# Power_supply.net
KiCad netlist of a schematic drawn in Altium Designer
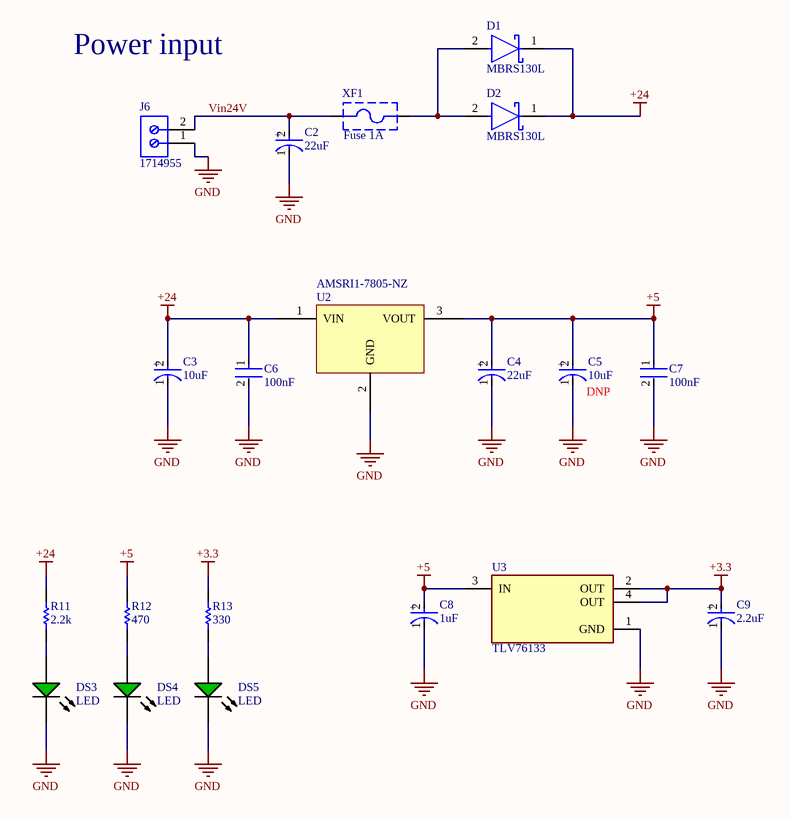
[diagram p0: Power_supply.SchDoc]

(export (version "E")
  (design (tool "Eeschema 10.0.6"))
  (components
    (comp (ref "C2")
      (value "22uF")
      (footprint "FP-FCE-MFG")
      (description "CAP ALUM 22UF 20% 50V SMD")
      (fields (field (name "VOLTAGE") "50V") (field (name "TOLERANCE") "20%"))
      (libsource (lib "Altium Content Vault") (part "a00bbbee19879c290e62620ae7e47b1"))
    )
    (comp (ref "C3")
      (value "10uF")
      (footprint "FP-FKD-MFG")
      (description "CAP ALUM 10UF 20% 50V SMD")
      (fields (field (name "VOLTAGE") "50V") (field (name "TOLERANCE") "20%"))
      (libsource (lib "Altium Content Vault") (part "203bc49f2ac43e59fd269a8c329ed05"))
    )
    (comp (ref "C4")
      (value "22uF")
      (footprint "FP-FCE-MFG")
      (description "CAP ALUM 22UF 20% 50V SMD")
      (fields (field (name "VOLTAGE") "50V") (field (name "TOLERANCE") "20%"))
      (libsource (lib "Altium Content Vault") (part "a00bbbee19879c290e62620ae7e47b1"))
    )
    (comp (ref "C5")
      (value "10uF")
      (footprint "FP-FKD-MFG")
      (description "CAP ALUM 10UF 20% 50V SMD")
      (fields (field (name "VOLTAGE") "50V") (field (name "TOLERANCE") "20%"))
      (libsource (lib "Altium Content Vault") (part "203bc49f2ac43e59fd269a8c329ed05"))
    )
    (comp (ref "C6")
      (value "100nF")
      (footprint "FP-0805-L_2_01_0_2-W_1_25-IPC_B")
      (description "General Purpose Ceramic Capacitor, 0805, 10nF, 10%, X7R, 15%, 100V")
      (fields (field (name "VOLTAGE") "100V") (field (name "TOLERANCE") "10%"))
      (libsource (lib "Altium Content Vault") (part "b4654b650e69147ec39a6b967a45e02"))
    )
    (comp (ref "C7")
      (value "100nF")
      (footprint "FP-0805-L_2_01_0_2-W_1_25-IPC_B")
      (description "General Purpose Ceramic Capacitor, 0805, 10nF, 10%, X7R, 15%, 100V")
      (fields (field (name "VOLTAGE") "100V") (field (name "TOLERANCE") "10%"))
      (libsource (lib "Altium Content Vault") (part "b4654b650e69147ec39a6b967a45e02"))
    )
    (comp (ref "C8")
      (value "1uF")
      (footprint "FP-FKD-MFG")
      (description "CAP ALUM 10UF 20% 50V SMD")
      (fields (field (name "VOLTAGE") "50V") (field (name "TOLERANCE") "20%"))
      (libsource (lib "Altium Content Vault") (part "203bc49f2ac43e59fd269a8c329ed05"))
    )
    (comp (ref "C9")
      (value "2.2uF")
      (footprint "FP-FKD-MFG")
      (description "CAP ALUM 10UF 20% 50V SMD")
      (fields (field (name "VOLTAGE") "50V") (field (name "TOLERANCE") "20%"))
      (libsource (lib "Altium Content Vault") (part "203bc49f2ac43e59fd269a8c329ed05"))
    )
    (comp (ref "D1")
      (value "MBRS130L")
      (footprint "FP-403AF-MFG")
      (description "MBRS130L Rectifier Diode, Schottky, 1 Phase, 1 Element, 2A, 30V V(RRM), Silicon, DO-214AA")
      (libsource (lib "Altium Content Vault") (part "1d6ec82d83fb6aee721767c19dac4b9"))
    )
    (comp (ref "D2")
      (value "MBRS130L")
      (footprint "FP-403AF-MFG")
      (description "MBRS130L Rectifier Diode, Schottky, 1 Phase, 1 Element, 2A, 30V V(RRM), Silicon, DO-214AA")
      (libsource (lib "Altium Content Vault") (part "1d6ec82d83fb6aee721767c19dac4b9"))
    )
    (comp (ref "DS3")
      (value "LED")
      (footprint "AVAG-HSMX-C170_V")
      (description "Chip LED, Green, 2.2 V, -40 to 85 degC, 2-Pin SMD, Pb-Free, Tape and Reel")
      (fields (field (name "MANUFACTURER") "Avago"))
      (libsource (lib "Altium Content Vault") (part "LED_GREEN_A1K2-2"))
    )
    (comp (ref "DS4")
      (value "LED")
      (footprint "AVAG-HSMX-C170_V")
      (description "Chip LED, Green, 2.2 V, -40 to 85 degC, 2-Pin SMD, Pb-Free, Tape and Reel")
      (fields (field (name "MANUFACTURER") "Avago"))
      (libsource (lib "Altium Content Vault") (part "LED_GREEN_A1K2-2"))
    )
    (comp (ref "DS5")
      (value "LED")
      (footprint "AVAG-HSMX-C170_V")
      (description "Chip LED, Green, 2.2 V, -40 to 85 degC, 2-Pin SMD, Pb-Free, Tape and Reel")
      (fields (field (name "MANUFACTURER") "Avago"))
      (libsource (lib "Altium Content Vault") (part "LED_GREEN_A1K2-2"))
    )
    (comp (ref "J6")
      (value "1714955")
      (footprint "PHOE-1714955_V")
      (description "PC Terminal Block, Pitch 6.35 mm, 1 x 2 Position, Height 21.5 mm, Tail Lenght 5.1 mm, RoHS, Bulk")
      (fields (field (name "MANUFACTURER") "Phoenix Contact"))
      (libsource (lib "Altium Content Vault") (part "CN-1P-F-TB2"))
    )
    (comp (ref "R11")
      (value "2.2k")
      (footprint "RESC2013X50X30LL20T20")
      (fields (field (name "MANUFACTURER") "Vishay Dale") (field (name "PART NUMBER") "CRCW08050000Z0EA"))
      (libsource (lib "Altium Content Vault") (part "RES"))
    )
    (comp (ref "R12")
      (value "470")
      (footprint "RESC2013X50X30LL20T20")
      (fields (field (name "MANUFACTURER") "Vishay Dale") (field (name "PART NUMBER") "CRCW08050000Z0EA"))
      (libsource (lib "Altium Content Vault") (part "RES"))
    )
    (comp (ref "R13")
      (value "330")
      (footprint "RESC2013X50X30LL20T20")
      (fields (field (name "MANUFACTURER") "Vishay Dale") (field (name "PART NUMBER") "CRCW08050000Z0EA"))
      (libsource (lib "Altium Content Vault") (part "RES"))
    )
    (comp (ref "U2")
      (value "AMSRI1-7805-NZ")
      (footprint "SIP750W46P254L1400H1010Q3")
      (description "AMSRI1-7805-NZ, 5V / 1A DC output converter")
      (libsource (lib "Schematic_library") (part "AMSRI1-7805-NZ"))
    )
    (comp (ref "U3")
      (value "TLV76133")
      (footprint "FP-DCY0004A-MFG")
      (description "TLV76133 1-A 16-V high-PSRR linear voltage regulator 4-SOT-223 -40 to 125")
      (libsource (lib "Altium Content Vault") (part "991ffb903c51cf6179ce9942c0606aa"))
    )
    (comp (ref "XF1")
      (value "Fuse 1A")
      (footprint "696106003002")
      (libsource (lib "Altium Content Vault") (part "Fuse Holder"))
    )
  )
  (nets
    (net (code "1") (name "+3.3") (class "Default")
      (node (ref "C9") (pin "2") (pinfunction "A_2") (pintype "passive"))
      (node (ref "R13") (pin "2") (pinfunction "2_2") (pintype "passive"))
      (node (ref "U3") (pin "2") (pinfunction "OUT_2") (pintype "passive"))
      (node (ref "U3") (pin "4") (pinfunction "OUT_4") (pintype "passive"))
    )
    (net (code "2") (name "+5") (class "Default")
      (node (ref "C4") (pin "2") (pinfunction "A_2") (pintype "passive"))
      (node (ref "C5") (pin "2") (pinfunction "A_2") (pintype "passive"))
      (node (ref "C7") (pin "1") (pinfunction "1_1") (pintype "passive"))
      (node (ref "C8") (pin "2") (pinfunction "A_2") (pintype "passive"))
      (node (ref "R12") (pin "2") (pinfunction "2_2") (pintype "passive"))
      (node (ref "U2") (pin "3") (pinfunction "VOUT_3") (pintype "passive"))
      (node (ref "U3") (pin "3") (pinfunction "IN_3") (pintype "power_in"))
    )
    (net (code "3") (name "+24") (class "Default")
      (node (ref "C3") (pin "2") (pinfunction "A_2") (pintype "passive"))
      (node (ref "C6") (pin "1") (pinfunction "1_1") (pintype "passive"))
      (node (ref "D1") (pin "1") (pinfunction "C_1") (pintype "passive"))
      (node (ref "D2") (pin "1") (pinfunction "C_1") (pintype "passive"))
      (node (ref "R11") (pin "2") (pinfunction "2_2") (pintype "passive"))
      (node (ref "U2") (pin "1") (pinfunction "VIN_1") (pintype "passive"))
    )
    (net (code "4") (name "/Vin24V") (class "Default")
      (node (ref "C2") (pin "2") (pinfunction "A_2") (pintype "passive"))
      (node (ref "J6") (pin "2") (pinfunction "2_2") (pintype "passive"))
      (node (ref "XF1") (pin "1") (pinfunction "1_1") (pintype "passive"))
    )
    (net (code "5") (name "GND") (class "Default")
      (node (ref "C2") (pin "1") (pinfunction "C_1") (pintype "passive"))
      (node (ref "C3") (pin "1") (pinfunction "C_1") (pintype "passive"))
      (node (ref "C4") (pin "1") (pinfunction "C_1") (pintype "passive"))
      (node (ref "C5") (pin "1") (pinfunction "C_1") (pintype "passive"))
      (node (ref "C6") (pin "2") (pinfunction "2_2") (pintype "passive"))
      (node (ref "C7") (pin "2") (pinfunction "2_2") (pintype "passive"))
      (node (ref "C8") (pin "1") (pinfunction "C_1") (pintype "passive"))
      (node (ref "C9") (pin "1") (pinfunction "C_1") (pintype "passive"))
      (node (ref "DS3") (pin "2") (pinfunction "K_2") (pintype "passive"))
      (node (ref "DS4") (pin "2") (pinfunction "K_2") (pintype "passive"))
      (node (ref "DS5") (pin "2") (pinfunction "K_2") (pintype "passive"))
      (node (ref "J6") (pin "1") (pinfunction "1_1") (pintype "passive"))
      (node (ref "U2") (pin "2") (pinfunction "GND_2") (pintype "passive"))
      (node (ref "U3") (pin "1") (pinfunction "GND_1") (pintype "power_in"))
    )
    (net (code "6") (name "Net-(D1-A)") (class "Default")
      (node (ref "D1") (pin "2") (pinfunction "A_2") (pintype "passive"))
      (node (ref "D2") (pin "2") (pinfunction "A_2") (pintype "passive"))
      (node (ref "XF1") (pin "2") (pinfunction "2_2") (pintype "passive"))
    )
    (net (code "7") (name "Net-(DS3-A)") (class "Default")
      (node (ref "DS3") (pin "1") (pinfunction "A_1") (pintype "passive"))
      (node (ref "R11") (pin "1") (pinfunction "1_1") (pintype "passive"))
    )
    (net (code "8") (name "Net-(DS4-A)") (class "Default")
      (node (ref "DS4") (pin "1") (pinfunction "A_1") (pintype "passive"))
      (node (ref "R12") (pin "1") (pinfunction "1_1") (pintype "passive"))
    )
    (net (code "9") (name "Net-(DS5-A)") (class "Default")
      (node (ref "DS5") (pin "1") (pinfunction "A_1") (pintype "passive"))
      (node (ref "R13") (pin "1") (pinfunction "1_1") (pintype "passive"))
    )
  )
)
